# CurrentConditioning.net
KiCad netlist of a schematic drawn in Altium Designer
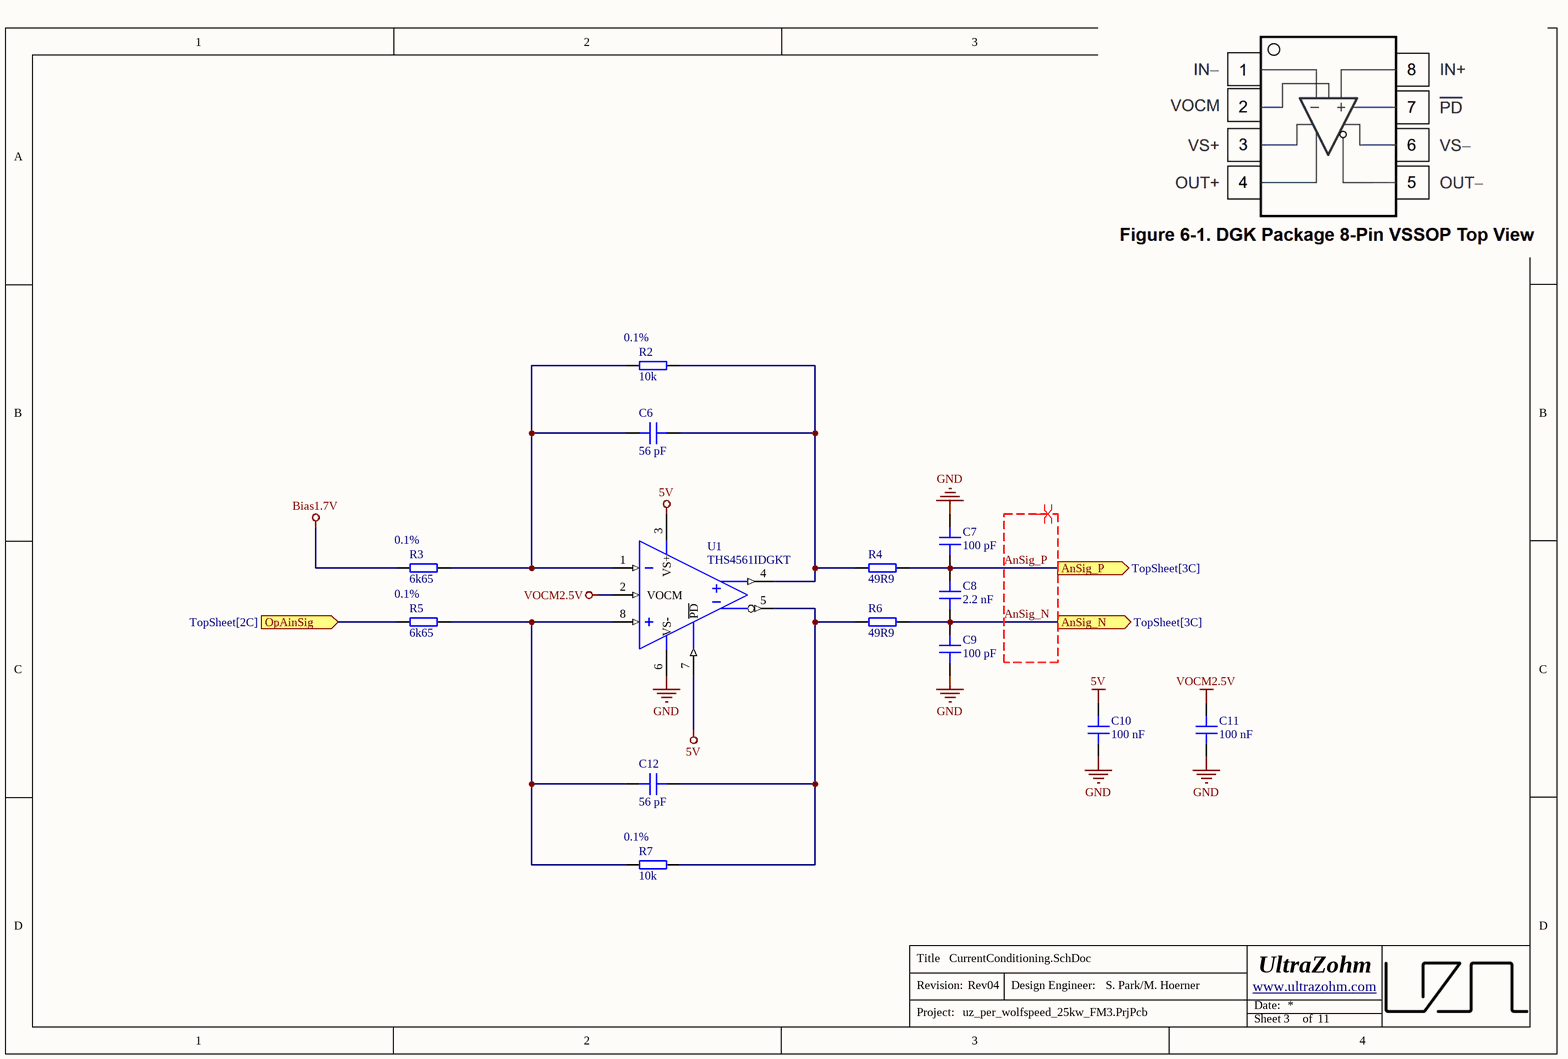
[diagram p0: CurrentConditioning.SchDoc]

(export (version "E")
  (design (tool "Eeschema 10.0.6"))
  (components
    (comp (ref "C6")
      (value "56 pF")
      (footprint "C_0603")
      (description "Capacitor 0603, 50 VDC, 56 pF, C0G")
      (fields
        (field (name "MANUFACTURER PART NUMBER") "CL10C560JB8NNNC")
        (field (name "MANUFACTURER") "Samsung Electro-Mechanics")
        (field (name "CREATED FROM") "DHufnagel")
      )
      (libsource (lib "user") (part "Capacitor"))
    )
    (comp (ref "C7")
      (value "100 pF")
      (footprint "C_0603_TE")
      (description "50V 100pF C0G ±5% 0603 Multilayer Ceramic Capacitors MLCC - SMD/SMT ROHS")
      (fields
        (field (name "MANUFACTURER PART NUMBER") "CL10C101JB8NNNC")
        (field (name "MANUFACTURER") "Samsung Electro-Mechanics")
        (field (name "CREATED FROM") "AGeiger")
      )
      (libsource (lib "user") (part "Capacitor"))
    )
    (comp (ref "C8")
      (value "2.2 nF")
      (footprint "C_0603")
      (description "Capacitor 0603, 50 VDC, 2.2 nF, X7R")
      (fields
        (field (name "MANUFACTURER PART NUMBER") "06035C222JAT2A")
        (field (name "MANUFACTURER") "AVX")
        (field (name "CREATED FROM") "MGremer")
      )
      (libsource (lib "user") (part "Capacitor"))
    )
    (comp (ref "C9")
      (value "100 pF")
      (footprint "C_0603_TE")
      (description "50V 100pF C0G ±5% 0603 Multilayer Ceramic Capacitors MLCC - SMD/SMT ROHS")
      (fields
        (field (name "MANUFACTURER PART NUMBER") "CL10C101JB8NNNC")
        (field (name "MANUFACTURER") "Samsung Electro-Mechanics")
        (field (name "CREATED FROM") "AGeiger")
      )
      (libsource (lib "user") (part "Capacitor"))
    )
    (comp (ref "C10")
      (value "100 nF")
      (footprint "C_0603")
      (description "Capacitor 0603, 50 VDC, 100nF, X7R")
      (fields
        (field (name "MANUFACTURER PART NUMBER") "C0603C104K5RAC3121")
        (field (name "MANUFACTURER") "KEMET")
        (field (name "CREATED FROM") "DHufnagel")
      )
      (libsource (lib "user") (part "Capacitor"))
    )
    (comp (ref "C11")
      (value "100 nF")
      (footprint "C_0603")
      (description "Capacitor 0603, 50 VDC, 100nF, X7R")
      (fields
        (field (name "MANUFACTURER PART NUMBER") "C0603C104K5RAC3121")
        (field (name "MANUFACTURER") "KEMET")
        (field (name "CREATED FROM") "DHufnagel")
      )
      (libsource (lib "user") (part "Capacitor"))
    )
    (comp (ref "C12")
      (value "56 pF")
      (footprint "C_0603")
      (description "Capacitor 0603, 50 VDC, 56 pF, C0G")
      (fields
        (field (name "MANUFACTURER PART NUMBER") "CL10C560JB8NNNC")
        (field (name "MANUFACTURER") "Samsung Electro-Mechanics")
        (field (name "CREATED FROM") "DHufnagel")
      )
      (libsource (lib "user") (part "Capacitor"))
    )
    (comp (ref "R2")
      (value "10k")
      (footprint "RES 0603_1608")
      (description "SMD resistor 0.1%, 10ppm")
      (fields
        (field (name "MANUFACTURER PART NUMBER") "ERA-3ARB103V")
        (field (name "MANUFACTURER") "Panasonic")
        (field (name "TOLERANCE") "0.1%")
        (field (name "CREATED FROM") "DHufnagel")
      )
      (libsource (lib "user") (part "Resistor"))
    )
    (comp (ref "R3")
      (value "6k65")
      (footprint "RES 0603_1608")
      (description "100mW Thin Film Resistor ±25ppm/℃ ±0.1% 6.65kΩ 0603 Chip Resistor - Surface Mount ROHS")
      (fields
        (field (name "MANUFACTURER PART NUMBER") "RT0603BRD076K65L")
        (field (name "MANUFACTURER") "YAGEO")
        (field (name "TOLERANCE") "0.1%")
        (field (name "CREATED FROM") "SPark")
      )
      (libsource (lib "user") (part "Resistor"))
    )
    (comp (ref "R4")
      (value "49R9")
      (footprint "RES 0603_1608")
      (description "SMD resistor 1%")
      (fields
        (field (name "MANUFACTURER PART NUMBER") "RK73H1JTTD49R9F")
        (field (name "MANUFACTURER") "KOA Speer")
        (field (name "CREATED FROM") "DHufnagel")
      )
      (libsource (lib "user") (part "Resistor"))
    )
    (comp (ref "R5")
      (value "6k65")
      (footprint "RES 0603_1608")
      (description "100mW Thin Film Resistor ±25ppm/℃ ±0.1% 6.65kΩ 0603 Chip Resistor - Surface Mount ROHS")
      (fields
        (field (name "MANUFACTURER PART NUMBER") "RT0603BRD076K65L")
        (field (name "MANUFACTURER") "YAGEO")
        (field (name "TOLERANCE") "0.1%")
        (field (name "CREATED FROM") "SPark")
      )
      (libsource (lib "user") (part "Resistor"))
    )
    (comp (ref "R6")
      (value "49R9")
      (footprint "RES 0603_1608")
      (description "SMD resistor 1%")
      (fields
        (field (name "MANUFACTURER PART NUMBER") "RK73H1JTTD49R9F")
        (field (name "MANUFACTURER") "KOA Speer")
        (field (name "CREATED FROM") "DHufnagel")
      )
      (libsource (lib "user") (part "Resistor"))
    )
    (comp (ref "R7")
      (value "10k")
      (footprint "RES 0603_1608")
      (description "SMD resistor 0.1%, 10ppm")
      (fields
        (field (name "MANUFACTURER PART NUMBER") "ERA-3ARB103V")
        (field (name "MANUFACTURER") "Panasonic")
        (field (name "TOLERANCE") "0.1%")
        (field (name "CREATED FROM") "DHufnagel")
      )
      (libsource (lib "user") (part "Resistor"))
    )
    (comp (ref "U1")
      (value "THS4561IDGKT")
      (footprint "SOP65P490X110-8N")
      (description "Fully Differential Amplifier, Low-Power, High Supply Range, 60-MHz")
      (fields
        (field (name "MANUFACTURER") "Texas Instruments")
        (field (name "LCSC PART NUMBER") "C2860980")
        (field (name "CREATED FROM") "DHufnagel")
      )
      (libsource (lib "user") (part "THS4561IDGKT"))
    )
  )
  (nets
    (net (code "1") (name "/AnSig_N") (class "Default")
      (node (ref "C8") (pin "2") (pinfunction "2_2") (pintype "passive"))
      (node (ref "C9") (pin "1") (pinfunction "1_1") (pintype "passive"))
      (node (ref "R6") (pin "2") (pinfunction "2_2") (pintype "passive"))
    )
    (net (code "2") (name "/AnSig_P") (class "Default")
      (node (ref "C7") (pin "2") (pinfunction "2_2") (pintype "passive"))
      (node (ref "C8") (pin "1") (pinfunction "1_1") (pintype "passive"))
      (node (ref "R4") (pin "2") (pinfunction "2_2") (pintype "passive"))
    )
    (net (code "3") (name "/OpAinSig") (class "Default")
      (node (ref "R5") (pin "1") (pinfunction "1_1") (pintype "passive"))
    )
    (net (code "4") (name "5V") (class "Default")
      (node (ref "C10") (pin "1") (pinfunction "1_1") (pintype "passive"))
      (node (ref "U1") (pin "3") (pinfunction "VS+_3") (pintype "power_in"))
      (node (ref "U1") (pin "7") (pinfunction "~{PD}_7") (pintype "input"))
    )
    (net (code "5") (name "Bias1.7V") (class "Default")
      (node (ref "R3") (pin "1") (pinfunction "1_1") (pintype "passive"))
    )
    (net (code "6") (name "GND") (class "Default")
      (node (ref "C10") (pin "2") (pinfunction "2_2") (pintype "passive"))
      (node (ref "C11") (pin "2") (pinfunction "2_2") (pintype "passive"))
      (node (ref "C7") (pin "1") (pinfunction "1_1") (pintype "passive"))
      (node (ref "C9") (pin "2") (pinfunction "2_2") (pintype "passive"))
      (node (ref "U1") (pin "6") (pinfunction "VS-_6") (pintype "power_in"))
    )
    (net (code "7") (name "Net-(U1-VIN+)") (class "Default")
      (node (ref "C12") (pin "1") (pinfunction "1_1") (pintype "passive"))
      (node (ref "R5") (pin "2") (pinfunction "2_2") (pintype "passive"))
      (node (ref "R7") (pin "1") (pinfunction "1_1") (pintype "passive"))
      (node (ref "U1") (pin "8") (pinfunction "VIN+_8") (pintype "input"))
    )
    (net (code "8") (name "Net-(U1-VIN-)") (class "Default")
      (node (ref "C6") (pin "1") (pinfunction "1_1") (pintype "passive"))
      (node (ref "R2") (pin "1") (pinfunction "1_1") (pintype "passive"))
      (node (ref "R3") (pin "2") (pinfunction "2_2") (pintype "passive"))
      (node (ref "U1") (pin "1") (pinfunction "VIN-_1") (pintype "input"))
    )
    (net (code "9") (name "Net-(U1-VOUT+)") (class "Default")
      (node (ref "C6") (pin "2") (pinfunction "2_2") (pintype "passive"))
      (node (ref "R2") (pin "2") (pinfunction "2_2") (pintype "passive"))
      (node (ref "R4") (pin "1") (pinfunction "1_1") (pintype "passive"))
      (node (ref "U1") (pin "4") (pinfunction "VOUT+_4") (pintype "output"))
    )
    (net (code "10") (name "Net-(U1-VOUT-)") (class "Default")
      (node (ref "C12") (pin "2") (pinfunction "2_2") (pintype "passive"))
      (node (ref "R6") (pin "1") (pinfunction "1_1") (pintype "passive"))
      (node (ref "R7") (pin "2") (pinfunction "2_2") (pintype "passive"))
      (node (ref "U1") (pin "5") (pinfunction "VOUT-_5") (pintype "output"))
    )
    (net (code "11") (name "VOCM2.5V") (class "Default")
      (node (ref "C11") (pin "1") (pinfunction "1_1") (pintype "passive"))
      (node (ref "U1") (pin "2") (pinfunction "VOCM_2") (pintype "input"))
    )
  )
)
